# untitled.net
KiCad netlist of a schematic drawn in EAGLE
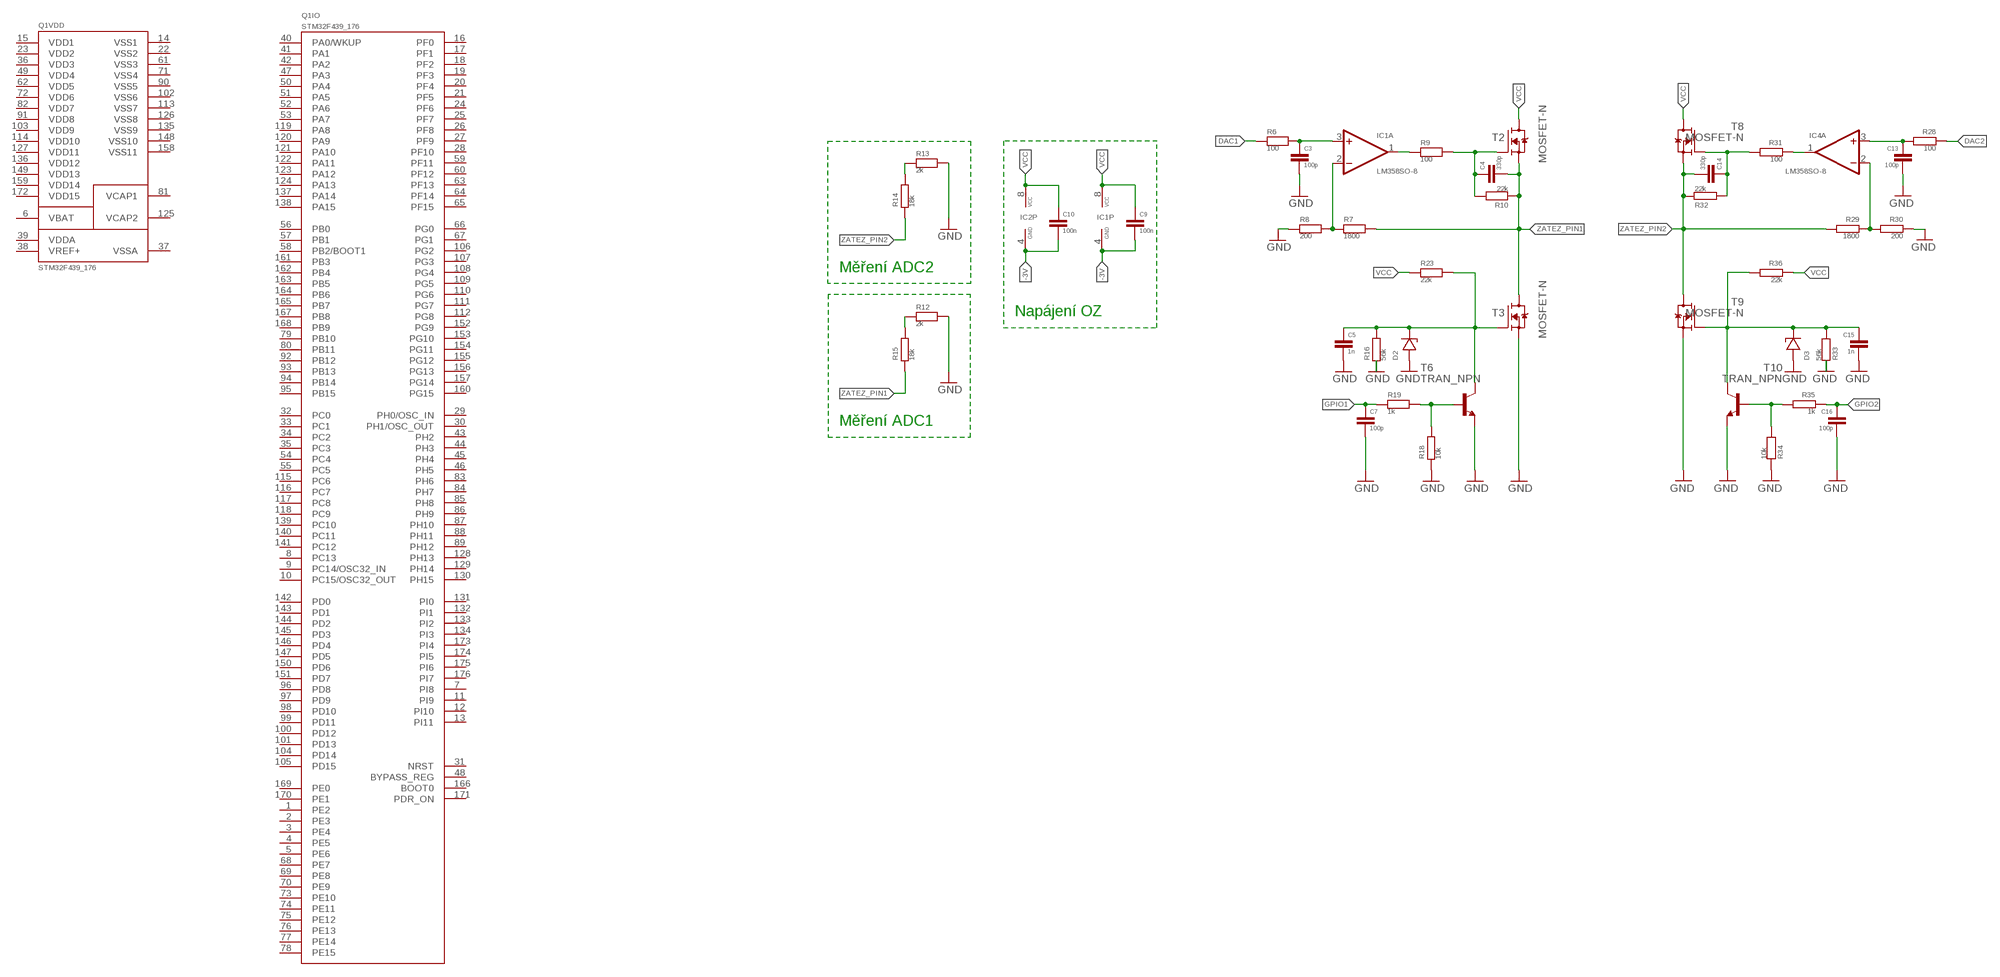
[diagram p0: schematic, sheet 1]

(export (version "E")
  (design (tool "Eeschema 10.0.6"))
  (components
    (comp (ref "C3")
      (value "100p")
      (footprint "eagle-import:0603")
      (libsource (lib "eagle-import") (part "C0603"))
    )
    (comp (ref "C4")
      (value "330p")
      (footprint "eagle-import:0603")
      (libsource (lib "eagle-import") (part "C0603"))
    )
    (comp (ref "C5")
      (value "1n")
      (footprint "eagle-import:0603")
      (libsource (lib "eagle-import") (part "C0603"))
    )
    (comp (ref "C7")
      (value "100p")
      (footprint "eagle-import:0603")
      (libsource (lib "eagle-import") (part "C0603"))
    )
    (comp (ref "C9")
      (value "100n")
      (footprint "eagle-import:0603")
      (libsource (lib "eagle-import") (part "C0603"))
    )
    (comp (ref "C10")
      (value "100n")
      (footprint "eagle-import:0603")
      (libsource (lib "eagle-import") (part "C0603"))
    )
    (comp (ref "C13")
      (value "100p")
      (footprint "eagle-import:0603")
      (libsource (lib "eagle-import") (part "C0603"))
    )
    (comp (ref "C14")
      (value "330p")
      (footprint "eagle-import:0603")
      (libsource (lib "eagle-import") (part "C0603"))
    )
    (comp (ref "C15")
      (value "1n")
      (footprint "eagle-import:0603")
      (libsource (lib "eagle-import") (part "C0603"))
    )
    (comp (ref "C16")
      (value "100p")
      (footprint "eagle-import:0603")
      (libsource (lib "eagle-import") (part "C0603"))
    )
    (comp (ref "D2")
      (value "D_ZENERSMA")
      (footprint "eagle-import:SMA")
      (libsource (lib "eagle-import") (part "D_ZENERSMA"))
    )
    (comp (ref "D3")
      (value "D_ZENERSMA")
      (footprint "eagle-import:SMA")
      (libsource (lib "eagle-import") (part "D_ZENERSMA"))
    )
    (comp (ref "IC1")
      (value "LM358SO-8")
      (footprint "eagle-import:SO-8")
      (libsource (lib "eagle-import") (part "LM358SO-8"))
    )
    (comp (ref "IC2")
      (value "LM358SO-8")
      (footprint "eagle-import:SO-8")
      (libsource (lib "eagle-import") (part "LM358SO-8"))
    )
    (comp (ref "IC4")
      (value "LM358SO-8")
      (footprint "eagle-import:SO-8")
      (libsource (lib "eagle-import") (part "LM358SO-8"))
    )
    (comp (ref "Q1")
      (value "STM32F439_176")
      (footprint "eagle-import:TQFP176")
      (libsource (lib "eagle-import") (part "STM32F439_176"))
    )
    (comp (ref "R6")
      (value "100")
      (footprint "eagle-import:0603")
      (libsource (lib "eagle-import") (part "R0603"))
    )
    (comp (ref "R7")
      (value "1800")
      (footprint "eagle-import:0603")
      (libsource (lib "eagle-import") (part "R0603"))
    )
    (comp (ref "R8")
      (value "200")
      (footprint "eagle-import:0603")
      (libsource (lib "eagle-import") (part "R0603"))
    )
    (comp (ref "R9")
      (value "100")
      (footprint "eagle-import:0603")
      (libsource (lib "eagle-import") (part "R0603"))
    )
    (comp (ref "R10")
      (value "22k")
      (footprint "eagle-import:0603")
      (libsource (lib "eagle-import") (part "R0603"))
    )
    (comp (ref "R12")
      (value "2k")
      (footprint "eagle-import:0603")
      (libsource (lib "eagle-import") (part "R0603"))
    )
    (comp (ref "R13")
      (value "2k")
      (footprint "eagle-import:0603")
      (libsource (lib "eagle-import") (part "R0603"))
    )
    (comp (ref "R14")
      (value "18k")
      (footprint "eagle-import:0603")
      (libsource (lib "eagle-import") (part "R0603"))
    )
    (comp (ref "R15")
      (value "18k")
      (footprint "eagle-import:0603")
      (libsource (lib "eagle-import") (part "R0603"))
    )
    (comp (ref "R16")
      (value "56k")
      (footprint "eagle-import:0603")
      (libsource (lib "eagle-import") (part "R0603"))
    )
    (comp (ref "R18")
      (value "10k")
      (footprint "eagle-import:0603")
      (libsource (lib "eagle-import") (part "R0603"))
    )
    (comp (ref "R19")
      (value "1k")
      (footprint "eagle-import:0603")
      (libsource (lib "eagle-import") (part "R0603"))
    )
    (comp (ref "R23")
      (value "22k")
      (footprint "eagle-import:0603")
      (libsource (lib "eagle-import") (part "R0603"))
    )
    (comp (ref "R28")
      (value "100")
      (footprint "eagle-import:0603")
      (libsource (lib "eagle-import") (part "R0603"))
    )
    (comp (ref "R29")
      (value "1800")
      (footprint "eagle-import:0603")
      (libsource (lib "eagle-import") (part "R0603"))
    )
    (comp (ref "R30")
      (value "200")
      (footprint "eagle-import:0603")
      (libsource (lib "eagle-import") (part "R0603"))
    )
    (comp (ref "R31")
      (value "100")
      (footprint "eagle-import:0603")
      (libsource (lib "eagle-import") (part "R0603"))
    )
    (comp (ref "R32")
      (value "22k")
      (footprint "eagle-import:0603")
      (libsource (lib "eagle-import") (part "R0603"))
    )
    (comp (ref "R33")
      (value "56k")
      (footprint "eagle-import:0603")
      (libsource (lib "eagle-import") (part "R0603"))
    )
    (comp (ref "R34")
      (value "10k")
      (footprint "eagle-import:0603")
      (libsource (lib "eagle-import") (part "R0603"))
    )
    (comp (ref "R35")
      (value "1k")
      (footprint "eagle-import:0603")
      (libsource (lib "eagle-import") (part "R0603"))
    )
    (comp (ref "R36")
      (value "22k")
      (footprint "eagle-import:0603")
      (libsource (lib "eagle-import") (part "R0603"))
    )
    (comp (ref "T2")
      (value "MOSFET-N")
      (footprint "eagle-import:TO220DL")
      (libsource (lib "eagle-import") (part "MOSFET-NTO220DL"))
    )
    (comp (ref "T3")
      (value "MOSFET-N")
      (footprint "eagle-import:TO220DL")
      (libsource (lib "eagle-import") (part "MOSFET-NTO220DL"))
    )
    (comp (ref "T6")
      (value "TRAN_NPN")
      (footprint "eagle-import:SOT23-3")
      (libsource (lib "eagle-import") (part "TRAN_NPN"))
    )
    (comp (ref "T8")
      (value "MOSFET-N")
      (footprint "eagle-import:TO220DL")
      (libsource (lib "eagle-import") (part "MOSFET-NTO220DL"))
    )
    (comp (ref "T9")
      (value "MOSFET-N")
      (footprint "eagle-import:TO220DL")
      (libsource (lib "eagle-import") (part "MOSFET-NTO220DL"))
    )
    (comp (ref "T10")
      (value "TRAN_NPN")
      (footprint "eagle-import:SOT23-3")
      (libsource (lib "eagle-import") (part "TRAN_NPN"))
    )
  )
  (nets
    (net (code "1") (name "-3V") (class "Default")
      (node (ref "C10") (pin "2") (pinfunction "2_2") (pintype "passive"))
      (node (ref "C9") (pin "2") (pinfunction "2_2") (pintype "passive"))
      (node (ref "IC1") (pin "4") (pinfunction "GND_4") (pintype "power_in"))
      (node (ref "IC2") (pin "4") (pinfunction "GND_4") (pintype "power_in"))
    )
    (net (code "2") (name "/VBAT") (class "Default")
      (node (ref "Q1") (pin "6") (pinfunction "VBAT_6") (pintype "power_in"))
    )
    (net (code "3") (name "/VDD1") (class "Default")
      (node (ref "Q1") (pin "15") (pinfunction "VDD1_15") (pintype "power_in"))
    )
    (net (code "4") (name "/VDD2") (class "Default")
      (node (ref "Q1") (pin "23") (pinfunction "VDD2_23") (pintype "power_in"))
    )
    (net (code "5") (name "/VDD3") (class "Default")
      (node (ref "Q1") (pin "36") (pinfunction "VDD3_36") (pintype "power_in"))
    )
    (net (code "6") (name "/VDD4") (class "Default")
      (node (ref "Q1") (pin "49") (pinfunction "VDD4_49") (pintype "power_in"))
    )
    (net (code "7") (name "/VDD5") (class "Default")
      (node (ref "Q1") (pin "62") (pinfunction "VDD5_62") (pintype "power_in"))
    )
    (net (code "8") (name "/VDD6") (class "Default")
      (node (ref "Q1") (pin "72") (pinfunction "VDD6_72") (pintype "power_in"))
    )
    (net (code "9") (name "/VDD7") (class "Default")
      (node (ref "Q1") (pin "82") (pinfunction "VDD7_82") (pintype "power_in"))
    )
    (net (code "10") (name "/VDD8") (class "Default")
      (node (ref "Q1") (pin "91") (pinfunction "VDD8_91") (pintype "power_in"))
    )
    (net (code "11") (name "/VDD9") (class "Default")
      (node (ref "Q1") (pin "103") (pinfunction "VDD9_103") (pintype "power_in"))
    )
    (net (code "12") (name "/VDD10") (class "Default")
      (node (ref "Q1") (pin "114") (pinfunction "VDD10_114") (pintype "power_in"))
    )
    (net (code "13") (name "/VDD11") (class "Default")
      (node (ref "Q1") (pin "127") (pinfunction "VDD11_127") (pintype "power_in"))
    )
    (net (code "14") (name "/VDD12") (class "Default")
      (node (ref "Q1") (pin "136") (pinfunction "VDD12_136") (pintype "power_in"))
    )
    (net (code "15") (name "/VDD13") (class "Default")
      (node (ref "Q1") (pin "149") (pinfunction "VDD13_149") (pintype "power_in"))
    )
    (net (code "16") (name "/VDD14") (class "Default")
      (node (ref "Q1") (pin "159") (pinfunction "VDD14_159") (pintype "power_in"))
    )
    (net (code "17") (name "/VDD15") (class "Default")
      (node (ref "Q1") (pin "172") (pinfunction "VDD15_172") (pintype "power_in"))
    )
    (net (code "18") (name "/VDDA") (class "Default")
      (node (ref "Q1") (pin "39") (pinfunction "VDDA_39") (pintype "power_in"))
    )
    (net (code "19") (name "/VSS1") (class "Default")
      (node (ref "Q1") (pin "14") (pinfunction "VSS1_14") (pintype "power_in"))
    )
    (net (code "20") (name "/VSS2") (class "Default")
      (node (ref "Q1") (pin "22") (pinfunction "VSS2_22") (pintype "power_in"))
    )
    (net (code "21") (name "/VSS3") (class "Default")
      (node (ref "Q1") (pin "61") (pinfunction "VSS3_61") (pintype "power_in"))
    )
    (net (code "22") (name "/VSS4") (class "Default")
      (node (ref "Q1") (pin "71") (pinfunction "VSS4_71") (pintype "power_in"))
    )
    (net (code "23") (name "/VSS5") (class "Default")
      (node (ref "Q1") (pin "90") (pinfunction "VSS5_90") (pintype "power_in"))
    )
    (net (code "24") (name "/VSS6") (class "Default")
      (node (ref "Q1") (pin "102") (pinfunction "VSS6_102") (pintype "power_in"))
    )
    (net (code "25") (name "/VSS7") (class "Default")
      (node (ref "Q1") (pin "113") (pinfunction "VSS7_113") (pintype "power_in"))
    )
    (net (code "26") (name "/VSS8") (class "Default")
      (node (ref "Q1") (pin "126") (pinfunction "VSS8_126") (pintype "power_in"))
    )
    (net (code "27") (name "/VSS9") (class "Default")
      (node (ref "Q1") (pin "135") (pinfunction "VSS9_135") (pintype "power_in"))
    )
    (net (code "28") (name "/VSS10") (class "Default")
      (node (ref "Q1") (pin "148") (pinfunction "VSS10_148") (pintype "power_in"))
    )
    (net (code "29") (name "/VSS11") (class "Default")
      (node (ref "Q1") (pin "158") (pinfunction "VSS11_158") (pintype "power_in"))
    )
    (net (code "30") (name "/VSSA") (class "Default")
      (node (ref "Q1") (pin "37") (pinfunction "VSSA_37") (pintype "power_in"))
    )
    (net (code "31") (name "DAC1") (class "Default")
      (node (ref "R6") (pin "1") (pinfunction "1_1") (pintype "passive"))
    )
    (net (code "32") (name "DAC2") (class "Default")
      (node (ref "R28") (pin "1") (pinfunction "1_1") (pintype "passive"))
    )
    (net (code "33") (name "GND") (class "Default")
      (node (ref "C13") (pin "2") (pinfunction "2_2") (pintype "passive"))
      (node (ref "C15") (pin "2") (pinfunction "2_2") (pintype "passive"))
      (node (ref "C16") (pin "2") (pinfunction "2_2") (pintype "passive"))
      (node (ref "C3") (pin "2") (pinfunction "2_2") (pintype "passive"))
      (node (ref "C5") (pin "2") (pinfunction "2_2") (pintype "passive"))
      (node (ref "C7") (pin "2") (pinfunction "2_2") (pintype "passive"))
      (node (ref "D2") (pin "A") (pinfunction "A_A") (pintype "bidirectional"))
      (node (ref "D3") (pin "A") (pinfunction "A_A") (pintype "bidirectional"))
      (node (ref "R12") (pin "2") (pinfunction "2_2") (pintype "passive"))
      (node (ref "R13") (pin "2") (pinfunction "2_2") (pintype "passive"))
      (node (ref "R16") (pin "1") (pinfunction "1_1") (pintype "passive"))
      (node (ref "R18") (pin "1") (pinfunction "1_1") (pintype "passive"))
      (node (ref "R30") (pin "1") (pinfunction "1_1") (pintype "passive"))
      (node (ref "R33") (pin "1") (pinfunction "1_1") (pintype "passive"))
      (node (ref "R34") (pin "1") (pinfunction "1_1") (pintype "passive"))
      (node (ref "R8") (pin "1") (pinfunction "1_1") (pintype "passive"))
      (node (ref "T10") (pin "2") (pinfunction "E_2") (pintype "passive"))
      (node (ref "T3") (pin "3") (pinfunction "S_3") (pintype "passive"))
      (node (ref "T6") (pin "2") (pinfunction "E_2") (pintype "passive"))
      (node (ref "T9") (pin "3") (pinfunction "S_3") (pintype "passive"))
    )
    (net (code "34") (name "GPIO1") (class "Default")
      (node (ref "C7") (pin "1") (pinfunction "1_1") (pintype "passive"))
      (node (ref "R19") (pin "1") (pinfunction "1_1") (pintype "passive"))
    )
    (net (code "35") (name "GPIO2") (class "Default")
      (node (ref "C16") (pin "1") (pinfunction "1_1") (pintype "passive"))
      (node (ref "R35") (pin "1") (pinfunction "1_1") (pintype "passive"))
    )
    (net (code "36") (name "Net-(D2-K)") (class "Default")
      (node (ref "C5") (pin "1") (pinfunction "1_1") (pintype "passive"))
      (node (ref "D2") (pin "C") (pinfunction "K_C") (pintype "bidirectional"))
      (node (ref "R16") (pin "2") (pinfunction "2_2") (pintype "passive"))
      (node (ref "R23") (pin "2") (pinfunction "2_2") (pintype "passive"))
      (node (ref "T3") (pin "1") (pinfunction "G_1") (pintype "passive"))
      (node (ref "T6") (pin "3") (pinfunction "C_3") (pintype "passive"))
    )
    (net (code "37") (name "Net-(D3-K)") (class "Default")
      (node (ref "C15") (pin "1") (pinfunction "1_1") (pintype "passive"))
      (node (ref "D3") (pin "C") (pinfunction "K_C") (pintype "bidirectional"))
      (node (ref "R33") (pin "2") (pinfunction "2_2") (pintype "passive"))
      (node (ref "R36") (pin "2") (pinfunction "2_2") (pintype "passive"))
      (node (ref "T10") (pin "3") (pinfunction "C_3") (pintype "passive"))
      (node (ref "T9") (pin "1") (pinfunction "G_1") (pintype "passive"))
    )
    (net (code "38") (name "Net-(IC1A-+IN)") (class "Default")
      (node (ref "C3") (pin "1") (pinfunction "1_1") (pintype "passive"))
      (node (ref "IC1") (pin "3") (pinfunction "+IN_3") (pintype "input"))
      (node (ref "R6") (pin "2") (pinfunction "2_2") (pintype "passive"))
    )
    (net (code "39") (name "Net-(IC1A--IN)") (class "Default")
      (node (ref "IC1") (pin "2") (pinfunction "-IN_2") (pintype "input"))
      (node (ref "R7") (pin "1") (pinfunction "1_1") (pintype "passive"))
      (node (ref "R8") (pin "2") (pinfunction "2_2") (pintype "passive"))
    )
    (net (code "40") (name "Net-(IC1A-OUT)") (class "Default")
      (node (ref "IC1") (pin "1") (pinfunction "OUT_1") (pintype "output"))
      (node (ref "R9") (pin "1") (pinfunction "1_1") (pintype "passive"))
    )
    (net (code "41") (name "Net-(IC4A-+IN)") (class "Default")
      (node (ref "C13") (pin "1") (pinfunction "1_1") (pintype "passive"))
      (node (ref "IC4") (pin "3") (pinfunction "+IN_3") (pintype "input"))
      (node (ref "R28") (pin "2") (pinfunction "2_2") (pintype "passive"))
    )
    (net (code "42") (name "Net-(IC4A--IN)") (class "Default")
      (node (ref "IC4") (pin "2") (pinfunction "-IN_2") (pintype "input"))
      (node (ref "R29") (pin "1") (pinfunction "1_1") (pintype "passive"))
      (node (ref "R30") (pin "2") (pinfunction "2_2") (pintype "passive"))
    )
    (net (code "43") (name "Net-(IC4A-OUT)") (class "Default")
      (node (ref "IC4") (pin "1") (pinfunction "OUT_1") (pintype "output"))
      (node (ref "R31") (pin "1") (pinfunction "1_1") (pintype "passive"))
    )
    (net (code "44") (name "Net-(R12-Pad1)") (class "Default")
      (node (ref "R12") (pin "1") (pinfunction "1_1") (pintype "passive"))
      (node (ref "R15") (pin "2") (pinfunction "2_2") (pintype "passive"))
    )
    (net (code "45") (name "Net-(R13-Pad1)") (class "Default")
      (node (ref "R13") (pin "1") (pinfunction "1_1") (pintype "passive"))
      (node (ref "R14") (pin "2") (pinfunction "2_2") (pintype "passive"))
    )
    (net (code "46") (name "Net-(T2-G)") (class "Default")
      (node (ref "C4") (pin "1") (pinfunction "1_1") (pintype "passive"))
      (node (ref "R10") (pin "2") (pinfunction "2_2") (pintype "passive"))
      (node (ref "R9") (pin "2") (pinfunction "2_2") (pintype "passive"))
      (node (ref "T2") (pin "1") (pinfunction "G_1") (pintype "passive"))
    )
    (net (code "47") (name "Net-(T6-B)") (class "Default")
      (node (ref "R18") (pin "2") (pinfunction "2_2") (pintype "passive"))
      (node (ref "R19") (pin "2") (pinfunction "2_2") (pintype "passive"))
      (node (ref "T6") (pin "1") (pinfunction "B_1") (pintype "passive"))
    )
    (net (code "48") (name "Net-(T8-G)") (class "Default")
      (node (ref "C14") (pin "1") (pinfunction "1_1") (pintype "passive"))
      (node (ref "R31") (pin "2") (pinfunction "2_2") (pintype "passive"))
      (node (ref "R32") (pin "2") (pinfunction "2_2") (pintype "passive"))
      (node (ref "T8") (pin "1") (pinfunction "G_1") (pintype "passive"))
    )
    (net (code "49") (name "Net-(T10-B)") (class "Default")
      (node (ref "R34") (pin "2") (pinfunction "2_2") (pintype "passive"))
      (node (ref "R35") (pin "2") (pinfunction "2_2") (pintype "passive"))
      (node (ref "T10") (pin "1") (pinfunction "B_1") (pintype "passive"))
    )
    (net (code "50") (name "VCC") (class "Default")
      (node (ref "C10") (pin "1") (pinfunction "1_1") (pintype "passive"))
      (node (ref "C9") (pin "1") (pinfunction "1_1") (pintype "passive"))
      (node (ref "IC1") (pin "8") (pinfunction "VCC_8") (pintype "power_in"))
      (node (ref "IC2") (pin "8") (pinfunction "VCC_8") (pintype "power_in"))
      (node (ref "R23") (pin "1") (pinfunction "1_1") (pintype "passive"))
      (node (ref "R36") (pin "1") (pinfunction "1_1") (pintype "passive"))
      (node (ref "T2") (pin "2") (pinfunction "D_2") (pintype "passive"))
      (node (ref "T8") (pin "2") (pinfunction "D_2") (pintype "passive"))
    )
    (net (code "51") (name "ZATEZ_PIN1") (class "Default")
      (node (ref "C4") (pin "2") (pinfunction "2_2") (pintype "passive"))
      (node (ref "R10") (pin "1") (pinfunction "1_1") (pintype "passive"))
      (node (ref "R15") (pin "1") (pinfunction "1_1") (pintype "passive"))
      (node (ref "R7") (pin "2") (pinfunction "2_2") (pintype "passive"))
      (node (ref "T2") (pin "3") (pinfunction "S_3") (pintype "passive"))
      (node (ref "T3") (pin "2") (pinfunction "D_2") (pintype "passive"))
    )
    (net (code "52") (name "ZATEZ_PIN2") (class "Default")
      (node (ref "C14") (pin "2") (pinfunction "2_2") (pintype "passive"))
      (node (ref "R14") (pin "1") (pinfunction "1_1") (pintype "passive"))
      (node (ref "R29") (pin "2") (pinfunction "2_2") (pintype "passive"))
      (node (ref "R32") (pin "1") (pinfunction "1_1") (pintype "passive"))
      (node (ref "T8") (pin "3") (pinfunction "S_3") (pintype "passive"))
      (node (ref "T9") (pin "2") (pinfunction "D_2") (pintype "passive"))
    )
    (net (code "53") (name "unconnected-(Q1A-BOOT0-Pad166)") (class "Default")
      (node (ref "Q1") (pin "166") (pinfunction "BOOT0_166") (pintype "bidirectional"))
    )
    (net (code "54") (name "unconnected-(Q1A-BYPASS_REG-Pad48)") (class "Default")
      (node (ref "Q1") (pin "48") (pinfunction "BYPASS_REG_48") (pintype "bidirectional"))
    )
    (net (code "55") (name "unconnected-(Q1A-NRST-Pad31)") (class "Default")
      (node (ref "Q1") (pin "31") (pinfunction "NRST_31") (pintype "bidirectional"))
    )
    (net (code "56") (name "unconnected-(Q1A-PA0{slash}WKUP-Pad40)") (class "Default")
      (node (ref "Q1") (pin "40") (pinfunction "PA0/WKUP_40") (pintype "bidirectional"))
    )
    (net (code "57") (name "unconnected-(Q1A-PA1-Pad41)") (class "Default")
      (node (ref "Q1") (pin "41") (pinfunction "PA1_41") (pintype "bidirectional"))
    )
    (net (code "58") (name "unconnected-(Q1A-PA2-Pad42)") (class "Default")
      (node (ref "Q1") (pin "42") (pinfunction "PA2_42") (pintype "bidirectional"))
    )
    (net (code "59") (name "unconnected-(Q1A-PA3-Pad47)") (class "Default")
      (node (ref "Q1") (pin "47") (pinfunction "PA3_47") (pintype "bidirectional"))
    )
    (net (code "60") (name "unconnected-(Q1A-PA4-Pad50)") (class "Default")
      (node (ref "Q1") (pin "50") (pinfunction "PA4_50") (pintype "bidirectional"))
    )
    (net (code "61") (name "unconnected-(Q1A-PA5-Pad51)") (class "Default")
      (node (ref "Q1") (pin "51") (pinfunction "PA5_51") (pintype "bidirectional"))
    )
    (net (code "62") (name "unconnected-(Q1A-PA6-Pad52)") (class "Default")
      (node (ref "Q1") (pin "52") (pinfunction "PA6_52") (pintype "bidirectional"))
    )
    (net (code "63") (name "unconnected-(Q1A-PA7-Pad53)") (class "Default")
      (node (ref "Q1") (pin "53") (pinfunction "PA7_53") (pintype "bidirectional"))
    )
    (net (code "64") (name "unconnected-(Q1A-PA8-Pad119)") (class "Default")
      (node (ref "Q1") (pin "119") (pinfunction "PA8_119") (pintype "bidirectional"))
    )
    (net (code "65") (name "unconnected-(Q1A-PA9-Pad120)") (class "Default")
      (node (ref "Q1") (pin "120") (pinfunction "PA9_120") (pintype "bidirectional"))
    )
    (net (code "66") (name "unconnected-(Q1A-PA10-Pad121)") (class "Default")
      (node (ref "Q1") (pin "121") (pinfunction "PA10_121") (pintype "bidirectional"))
    )
    (net (code "67") (name "unconnected-(Q1A-PA11-Pad122)") (class "Default")
      (node (ref "Q1") (pin "122") (pinfunction "PA11_122") (pintype "bidirectional"))
    )
    (net (code "68") (name "unconnected-(Q1A-PA12-Pad123)") (class "Default")
      (node (ref "Q1") (pin "123") (pinfunction "PA12_123") (pintype "bidirectional"))
    )
    (net (code "69") (name "unconnected-(Q1A-PA13-Pad124)") (class "Default")
      (node (ref "Q1") (pin "124") (pinfunction "PA13_124") (pintype "bidirectional"))
    )
    (net (code "70") (name "unconnected-(Q1A-PA14-Pad137)") (class "Default")
      (node (ref "Q1") (pin "137") (pinfunction "PA14_137") (pintype "bidirectional"))
    )
    (net (code "71") (name "unconnected-(Q1A-PA15-Pad138)") (class "Default")
      (node (ref "Q1") (pin "138") (pinfunction "PA15_138") (pintype "bidirectional"))
    )
    (net (code "72") (name "unconnected-(Q1A-PB0-Pad56)") (class "Default")
      (node (ref "Q1") (pin "56") (pinfunction "PB0_56") (pintype "bidirectional"))
    )
    (net (code "73") (name "unconnected-(Q1A-PB1-Pad57)") (class "Default")
      (node (ref "Q1") (pin "57") (pinfunction "PB1_57") (pintype "bidirectional"))
    )
    (net (code "74") (name "unconnected-(Q1A-PB2{slash}BOOT1-Pad58)") (class "Default")
      (node (ref "Q1") (pin "58") (pinfunction "PB2/BOOT1_58") (pintype "bidirectional"))
    )
    (net (code "75") (name "unconnected-(Q1A-PB3-Pad161)") (class "Default")
      (node (ref "Q1") (pin "161") (pinfunction "PB3_161") (pintype "bidirectional"))
    )
    (net (code "76") (name "unconnected-(Q1A-PB4-Pad162)") (class "Default")
      (node (ref "Q1") (pin "162") (pinfunction "PB4_162") (pintype "bidirectional"))
    )
    (net (code "77") (name "unconnected-(Q1A-PB5-Pad163)") (class "Default")
      (node (ref "Q1") (pin "163") (pinfunction "PB5_163") (pintype "bidirectional"))
    )
    (net (code "78") (name "unconnected-(Q1A-PB6-Pad164)") (class "Default")
      (node (ref "Q1") (pin "164") (pinfunction "PB6_164") (pintype "bidirectional"))
    )
    (net (code "79") (name "unconnected-(Q1A-PB7-Pad165)") (class "Default")
      (node (ref "Q1") (pin "165") (pinfunction "PB7_165") (pintype "bidirectional"))
    )
    (net (code "80") (name "unconnected-(Q1A-PB8-Pad167)") (class "Default")
      (node (ref "Q1") (pin "167") (pinfunction "PB8_167") (pintype "bidirectional"))
    )
    (net (code "81") (name "unconnected-(Q1A-PB9-Pad168)") (class "Default")
      (node (ref "Q1") (pin "168") (pinfunction "PB9_168") (pintype "bidirectional"))
    )
    (net (code "82") (name "unconnected-(Q1A-PB10-Pad79)") (class "Default")
      (node (ref "Q1") (pin "79") (pinfunction "PB10_79") (pintype "bidirectional"))
    )
    (net (code "83") (name "unconnected-(Q1A-PB11-Pad80)") (class "Default")
      (node (ref "Q1") (pin "80") (pinfunction "PB11_80") (pintype "bidirectional"))
    )
    (net (code "84") (name "unconnected-(Q1A-PB12-Pad92)") (class "Default")
      (node (ref "Q1") (pin "92") (pinfunction "PB12_92") (pintype "bidirectional"))
    )
    (net (code "85") (name "unconnected-(Q1A-PB13-Pad93)") (class "Default")
      (node (ref "Q1") (pin "93") (pinfunction "PB13_93") (pintype "bidirectional"))
    )
    (net (code "86") (name "unconnected-(Q1A-PB14-Pad94)") (class "Default")
      (node (ref "Q1") (pin "94") (pinfunction "PB14_94") (pintype "bidirectional"))
    )
    (net (code "87") (name "unconnected-(Q1A-PB15-Pad95)") (class "Default")
      (node (ref "Q1") (pin "95") (pinfunction "PB15_95") (pintype "bidirectional"))
    )
    (net (code "88") (name "unconnected-(Q1A-PC0-Pad32)") (class "Default")
      (node (ref "Q1") (pin "32") (pinfunction "PC0_32") (pintype "bidirectional"))
    )
    (net (code "89") (name "unconnected-(Q1A-PC1-Pad33)") (class "Default")
      (node (ref "Q1") (pin "33") (pinfunction "PC1_33") (pintype "bidirectional"))
    )
    (net (code "90") (name "unconnected-(Q1A-PC2-Pad34)") (class "Default")
      (node (ref "Q1") (pin "34") (pinfunction "PC2_34") (pintype "bidirectional"))
    )
    (net (code "91") (name "unconnected-(Q1A-PC3-Pad35)") (class "Default")
      (node (ref "Q1") (pin "35") (pinfunction "PC3_35") (pintype "bidirectional"))
    )
    (net (code "92") (name "unconnected-(Q1A-PC4-Pad54)") (class "Default")
      (node (ref "Q1") (pin "54") (pinfunction "PC4_54") (pintype "bidirectional"))
    )
    (net (code "93") (name "unconnected-(Q1A-PC5-Pad55)") (class "Default")
      (node (ref "Q1") (pin "55") (pinfunction "PC5_55") (pintype "bidirectional"))
    )
    (net (code "94") (name "unconnected-(Q1A-PC6-Pad115)") (class "Default")
      (node (ref "Q1") (pin "115") (pinfunction "PC6_115") (pintype "bidirectional"))
    )
    (net (code "95") (name "unconnected-(Q1A-PC7-Pad116)") (class "Default")
      (node (ref "Q1") (pin "116") (pinfunction "PC7_116") (pintype "bidirectional"))
    )
    (net (code "96") (name "unconnected-(Q1A-PC8-Pad117)") (class "Default")
      (node (ref "Q1") (pin "117") (pinfunction "PC8_117") (pintype "bidirectional"))
    )
    (net (code "97") (name "unconnected-(Q1A-PC9-Pad118)") (class "Default")
      (node (ref "Q1") (pin "118") (pinfunction "PC9_118") (pintype "bidirectional"))
    )
    (net (code "98") (name "unconnected-(Q1A-PC10-Pad139)") (class "Default")
      (node (ref "Q1") (pin "139") (pinfunction "PC10_139") (pintype "bidirectional"))
    )
    (net (code "99") (name "unconnected-(Q1A-PC11-Pad140)") (class "Default")
      (node (ref "Q1") (pin "140") (pinfunction "PC11_140") (pintype "bidirectional"))
    )
    (net (code "100") (name "unconnected-(Q1A-PC12-Pad141)") (class "Default")
      (node (ref "Q1") (pin "141") (pinfunction "PC12_141") (pintype "bidirectional"))
    )
    (net (code "101") (name "unconnected-(Q1A-PC13-Pad8)") (class "Default")
      (node (ref "Q1") (pin "8") (pinfunction "PC13_8") (pintype "bidirectional"))
    )
    (net (code "102") (name "unconnected-(Q1A-PC14{slash}OSC32_IN-Pad9)") (class "Default")
      (node (ref "Q1") (pin "9") (pinfunction "PC14/OSC32_IN_9") (pintype "bidirectional"))
    )
    (net (code "103") (name "unconnected-(Q1A-PC15{slash}OSC32_OUT-Pad10)") (class "Default")
      (node (ref "Q1") (pin "10") (pinfunction "PC15/OSC32_OUT_10") (pintype "bidirectional"))
    )
    (net (code "104") (name "unconnected-(Q1A-PD0-Pad142)") (class "Default")
      (node (ref "Q1") (pin "142") (pinfunction "PD0_142") (pintype "bidirectional"))
    )
    (net (code "105") (name "unconnected-(Q1A-PD1-Pad143)") (class "Default")
      (node (ref "Q1") (pin "143") (pinfunction "PD1_143") (pintype "bidirectional"))
    )
    (net (code "106") (name "unconnected-(Q1A-PD2-Pad144)") (class "Default")
      (node (ref "Q1") (pin "144") (pinfunction "PD2_144") (pintype "bidirectional"))
    )
    (net (code "107") (name "unconnected-(Q1A-PD3-Pad145)") (class "Default")
      (node (ref "Q1") (pin "145") (pinfunction "PD3_145") (pintype "bidirectional"))
    )
    (net (code "108") (name "unconnected-(Q1A-PD4-Pad146)") (class "Default")
      (node (ref "Q1") (pin "146") (pinfunction "PD4_146") (pintype "bidirectional"))
    )
    (net (code "109") (name "unconnected-(Q1A-PD5-Pad147)") (class "Default")
      (node (ref "Q1") (pin "147") (pinfunction "PD5_147") (pintype "bidirectional"))
    )
    (net (code "110") (name "unconnected-(Q1A-PD6-Pad150)") (class "Default")
      (node (ref "Q1") (pin "150") (pinfunction "PD6_150") (pintype "bidirectional"))
    )
    (net (code "111") (name "unconnected-(Q1A-PD7-Pad151)") (class "Default")
      (node (ref "Q1") (pin "151") (pinfunction "PD7_151") (pintype "bidirectional"))
    )
    (net (code "112") (name "unconnected-(Q1A-PD8-Pad96)") (class "Default")
      (node (ref "Q1") (pin "96") (pinfunction "PD8_96") (pintype "bidirectional"))
    )
    (net (code "113") (name "unconnected-(Q1A-PD9-Pad97)") (class "Default")
      (node (ref "Q1") (pin "97") (pinfunction "PD9_97") (pintype "bidirectional"))
    )
    (net (code "114") (name "unconnected-(Q1A-PD10-Pad98)") (class "Default")
      (node (ref "Q1") (pin "98") (pinfunction "PD10_98") (pintype "bidirectional"))
    )
    (net (code "115") (name "unconnected-(Q1A-PD11-Pad99)") (class "Default")
      (node (ref "Q1") (pin "99") (pinfunction "PD11_99") (pintype "bidirectional"))
    )
    (net (code "116") (name "unconnected-(Q1A-PD12-Pad100)") (class "Default")
      (node (ref "Q1") (pin "100") (pinfunction "PD12_100") (pintype "bidirectional"))
    )
    (net (code "117") (name "unconnected-(Q1A-PD13-Pad101)") (class "Default")
      (node (ref "Q1") (pin "101") (pinfunction "PD13_101") (pintype "bidirectional"))
    )
    (net (code "118") (name "unconnected-(Q1A-PD14-Pad104)") (class "Default")
      (node (ref "Q1") (pin "104") (pinfunction "PD14_104") (pintype "bidirectional"))
    )
    (net (code "119") (name "unconnected-(Q1A-PD15-Pad105)") (class "Default")
      (node (ref "Q1") (pin "105") (pinfunction "PD15_105") (pintype "bidirectional"))
    )
    (net (code "120") (name "unconnected-(Q1A-PDR_ON-Pad171)") (class "Default")
      (node (ref "Q1") (pin "171") (pinfunction "PDR_ON_171") (pintype "bidirectional"))
    )
    (net (code "121") (name "unconnected-(Q1A-PE0-Pad169)") (class "Default")
      (node (ref "Q1") (pin "169") (pinfunction "PE0_169") (pintype "bidirectional"))
    )
    (net (code "122") (name "unconnected-(Q1A-PE1-Pad170)") (class "Default")
      (node (ref "Q1") (pin "170") (pinfunction "PE1_170") (pintype "bidirectional"))
    )
    (net (code "123") (name "unconnected-(Q1A-PE2-Pad1)") (class "Default")
      (node (ref "Q1") (pin "1") (pinfunction "PE2_1") (pintype "bidirectional"))
    )
    (net (code "124") (name "unconnected-(Q1A-PE3-Pad2)") (class "Default")
      (node (ref "Q1") (pin "2") (pinfunction "PE3_2") (pintype "bidirectional"))
    )
    (net (code "125") (name "unconnected-(Q1A-PE4-Pad3)") (class "Default")
      (node (ref "Q1") (pin "3") (pinfunction "PE4_3") (pintype "bidirectional"))
    )
    (net (code "126") (name "unconnected-(Q1A-PE5-Pad4)") (class "Default")
      (node (ref "Q1") (pin "4") (pinfunction "PE5_4") (pintype "bidirectional"))
    )
    (net (code "127") (name "unconnected-(Q1A-PE6-Pad5)") (class "Default")
      (node (ref "Q1") (pin "5") (pinfunction "PE6_5") (pintype "bidirectional"))
    )
    (net (code "128") (name "unconnected-(Q1A-PE7-Pad68)") (class "Default")
      (node (ref "Q1") (pin "68") (pinfunction "PE7_68") (pintype "bidirectional"))
    )
    (net (code "129") (name "unconnected-(Q1A-PE8-Pad69)") (class "Default")
      (node (ref "Q1") (pin "69") (pinfunction "PE8_69") (pintype "bidirectional"))
    )
    (net (code "130") (name "unconnected-(Q1A-PE9-Pad70)") (class "Default")
      (node (ref "Q1") (pin "70") (pinfunction "PE9_70") (pintype "bidirectional"))
    )
    (net (code "131") (name "unconnected-(Q1A-PE10-Pad73)") (class "Default")
      (node (ref "Q1") (pin "73") (pinfunction "PE10_73") (pintype "bidirectional"))
    )
    (net (code "132") (name "unconnected-(Q1A-PE11-Pad74)") (class "Default")
      (node (ref "Q1") (pin "74") (pinfunction "PE11_74") (pintype "bidirectional"))
    )
    (net (code "133") (name "unconnected-(Q1A-PE12-Pad75)") (class "Default")
      (node (ref "Q1") (pin "75") (pinfunction "PE12_75") (pintype "bidirectional"))
    )
    (net (code "134") (name "unconnected-(Q1A-PE13-Pad76)") (class "Default")
      (node (ref "Q1") (pin "76") (pinfunction "PE13_76") (pintype "bidirectional"))
    )
    (net (code "135") (name "unconnected-(Q1A-PE14-Pad77)") (class "Default")
      (node (ref "Q1") (pin "77") (pinfunction "PE14_77") (pintype "bidirectional"))
    )
    (net (code "136") (name "unconnected-(Q1A-PE15-Pad78)") (class "Default")
      (node (ref "Q1") (pin "78") (pinfunction "PE15_78") (pintype "bidirectional"))
    )
    (net (code "137") (name "unconnected-(Q1A-PF0-Pad16)") (class "Default")
      (node (ref "Q1") (pin "16") (pinfunction "PF0_16") (pintype "bidirectional"))
    )
    (net (code "138") (name "unconnected-(Q1A-PF1-Pad17)") (class "Default")
      (node (ref "Q1") (pin "17") (pinfunction "PF1_17") (pintype "bidirectional"))
    )
    (net (code "139") (name "unconnected-(Q1A-PF2-Pad18)") (class "Default")
      (node (ref "Q1") (pin "18") (pinfunction "PF2_18") (pintype "bidirectional"))
    )
    (net (code "140") (name "unconnected-(Q1A-PF3-Pad19)") (class "Default")
      (node (ref "Q1") (pin "19") (pinfunction "PF3_19") (pintype "bidirectional"))
    )
    (net (code "141") (name "unconnected-(Q1A-PF4-Pad20)") (class "Default")
      (node (ref "Q1") (pin "20") (pinfunction "PF4_20") (pintype "bidirectional"))
    )
    (net (code "142") (name "unconnected-(Q1A-PF5-Pad21)") (class "Default")
      (node (ref "Q1") (pin "21") (pinfunction "PF5_21") (pintype "bidirectional"))
    )
    (net (code "143") (name "unconnected-(Q1A-PF6-Pad24)") (class "Default")
      (node (ref "Q1") (pin "24") (pinfunction "PF6_24") (pintype "bidirectional"))
    )
    (net (code "144") (name "unconnected-(Q1A-PF7-Pad25)") (class "Default")
      (node (ref "Q1") (pin "25") (pinfunction "PF7_25") (pintype "bidirectional"))
    )
    (net (code "145") (name "unconnected-(Q1A-PF8-Pad26)") (class "Default")
      (node (ref "Q1") (pin "26") (pinfunction "PF8_26") (pintype "bidirectional"))
    )
    (net (code "146") (name "unconnected-(Q1A-PF9-Pad27)") (class "Default")
      (node (ref "Q1") (pin "27") (pinfunction "PF9_27") (pintype "bidirectional"))
    )
    (net (code "147") (name "unconnected-(Q1A-PF10-Pad28)") (class "Default")
      (node (ref "Q1") (pin "28") (pinfunction "PF10_28") (pintype "bidirectional"))
    )
    (net (code "148") (name "unconnected-(Q1A-PF11-Pad59)") (class "Default")
      (node (ref "Q1") (pin "59") (pinfunction "PF11_59") (pintype "bidirectional"))
    )
    (net (code "149") (name "unconnected-(Q1A-PF12-Pad60)") (class "Default")
      (node (ref "Q1") (pin "60") (pinfunction "PF12_60") (pintype "bidirectional"))
    )
    (net (code "150") (name "unconnected-(Q1A-PF13-Pad63)") (class "Default")
      (node (ref "Q1") (pin "63") (pinfunction "PF13_63") (pintype "bidirectional"))
    )
    (net (code "151") (name "unconnected-(Q1A-PF14-Pad64)") (class "Default")
      (node (ref "Q1") (pin "64") (pinfunction "PF14_64") (pintype "bidirectional"))
    )
    (net (code "152") (name "unconnected-(Q1A-PF15-Pad65)") (class "Default")
      (node (ref "Q1") (pin "65") (pinfunction "PF15_65") (pintype "bidirectional"))
    )
    (net (code "153") (name "unconnected-(Q1A-PG0-Pad66)") (class "Default")
      (node (ref "Q1") (pin "66") (pinfunction "PG0_66") (pintype "bidirectional"))
    )
    (net (code "154") (name "unconnected-(Q1A-PG1-Pad67)") (class "Default")
      (node (ref "Q1") (pin "67") (pinfunction "PG1_67") (pintype "bidirectional"))
    )
    (net (code "155") (name "unconnected-(Q1A-PG2-Pad106)") (class "Default")
      (node (ref "Q1") (pin "106") (pinfunction "PG2_106") (pintype "bidirectional"))
    )
    (net (code "156") (name "unconnected-(Q1A-PG3-Pad107)") (class "Default")
      (node (ref "Q1") (pin "107") (pinfunction "PG3_107") (pintype "bidirectional"))
    )
    (net (code "157") (name "unconnected-(Q1A-PG4-Pad108)") (class "Default")
      (node (ref "Q1") (pin "108") (pinfunction "PG4_108") (pintype "bidirectional"))
    )
    (net (code "158") (name "unconnected-(Q1A-PG5-Pad109)") (class "Default")
      (node (ref "Q1") (pin "109") (pinfunction "PG5_109") (pintype "bidirectional"))
    )
    (net (code "159") (name "unconnected-(Q1A-PG6-Pad110)") (class "Default")
      (node (ref "Q1") (pin "110") (pinfunction "PG6_110") (pintype "bidirectional"))
    )
    (net (code "160") (name "unconnected-(Q1A-PG7-Pad111)") (class "Default")
      (node (ref "Q1") (pin "111") (pinfunction "PG7_111") (pintype "bidirectional"))
    )
    (net (code "161") (name "unconnected-(Q1A-PG8-Pad112)") (class "Default")
      (node (ref "Q1") (pin "112") (pinfunction "PG8_112") (pintype "bidirectional"))
    )
    (net (code "162") (name "unconnected-(Q1A-PG9-Pad152)") (class "Default")
      (node (ref "Q1") (pin "152") (pinfunction "PG9_152") (pintype "bidirectional"))
    )
    (net (code "163") (name "unconnected-(Q1A-PG10-Pad153)") (class "Default")
      (node (ref "Q1") (pin "153") (pinfunction "PG10_153") (pintype "bidirectional"))
    )
    (net (code "164") (name "unconnected-(Q1A-PG11-Pad154)") (class "Default")
      (node (ref "Q1") (pin "154") (pinfunction "PG11_154") (pintype "bidirectional"))
    )
    (net (code "165") (name "unconnected-(Q1A-PG12-Pad155)") (class "Default")
      (node (ref "Q1") (pin "155") (pinfunction "PG12_155") (pintype "bidirectional"))
    )
    (net (code "166") (name "unconnected-(Q1A-PG13-Pad156)") (class "Default")
      (node (ref "Q1") (pin "156") (pinfunction "PG13_156") (pintype "bidirectional"))
    )
    (net (code "167") (name "unconnected-(Q1A-PG14-Pad157)") (class "Default")
      (node (ref "Q1") (pin "157") (pinfunction "PG14_157") (pintype "bidirectional"))
    )
    (net (code "168") (name "unconnected-(Q1A-PG15-Pad160)") (class "Default")
      (node (ref "Q1") (pin "160") (pinfunction "PG15_160") (pintype "bidirectional"))
    )
    (net (code "169") (name "unconnected-(Q1A-PH0{slash}OSC_IN-Pad29)") (class "Default")
      (node (ref "Q1") (pin "29") (pinfunction "PH0/OSC_IN_29") (pintype "bidirectional"))
    )
    (net (code "170") (name "unconnected-(Q1A-PH1{slash}OSC_OUT-Pad30)") (class "Default")
      (node (ref "Q1") (pin "30") (pinfunction "PH1/OSC_OUT_30") (pintype "bidirectional"))
    )
    (net (code "171") (name "unconnected-(Q1A-PH2-Pad43)") (class "Default")
      (node (ref "Q1") (pin "43") (pinfunction "PH2_43") (pintype "bidirectional"))
    )
    (net (code "172") (name "unconnected-(Q1A-PH3-Pad44)") (class "Default")
      (node (ref "Q1") (pin "44") (pinfunction "PH3_44") (pintype "bidirectional"))
    )
    (net (code "173") (name "unconnected-(Q1A-PH4-Pad45)") (class "Default")
      (node (ref "Q1") (pin "45") (pinfunction "PH4_45") (pintype "bidirectional"))
    )
    (net (code "174") (name "unconnected-(Q1A-PH5-Pad46)") (class "Default")
      (node (ref "Q1") (pin "46") (pinfunction "PH5_46") (pintype "bidirectional"))
    )
    (net (code "175") (name "unconnected-(Q1A-PH6-Pad83)") (class "Default")
      (node (ref "Q1") (pin "83") (pinfunction "PH6_83") (pintype "bidirectional"))
    )
    (net (code "176") (name "unconnected-(Q1A-PH7-Pad84)") (class "Default")
      (node (ref "Q1") (pin "84") (pinfunction "PH7_84") (pintype "bidirectional"))
    )
    (net (code "177") (name "unconnected-(Q1A-PH8-Pad85)") (class "Default")
      (node (ref "Q1") (pin "85") (pinfunction "PH8_85") (pintype "bidirectional"))
    )
    (net (code "178") (name "unconnected-(Q1A-PH9-Pad86)") (class "Default")
      (node (ref "Q1") (pin "86") (pinfunction "PH9_86") (pintype "bidirectional"))
    )
    (net (code "179") (name "unconnected-(Q1A-PH10-Pad87)") (class "Default")
      (node (ref "Q1") (pin "87") (pinfunction "PH10_87") (pintype "bidirectional"))
    )
    (net (code "180") (name "unconnected-(Q1A-PH11-Pad88)") (class "Default")
      (node (ref "Q1") (pin "88") (pinfunction "PH11_88") (pintype "bidirectional"))
    )
    (net (code "181") (name "unconnected-(Q1A-PH12-Pad89)") (class "Default")
      (node (ref "Q1") (pin "89") (pinfunction "PH12_89") (pintype "bidirectional"))
    )
    (net (code "182") (name "unconnected-(Q1A-PH13-Pad128)") (class "Default")
      (node (ref "Q1") (pin "128") (pinfunction "PH13_128") (pintype "bidirectional"))
    )
    (net (code "183") (name "unconnected-(Q1A-PH14-Pad129)") (class "Default")
      (node (ref "Q1") (pin "129") (pinfunction "PH14_129") (pintype "bidirectional"))
    )
    (net (code "184") (name "unconnected-(Q1A-PH15-Pad130)") (class "Default")
      (node (ref "Q1") (pin "130") (pinfunction "PH15_130") (pintype "bidirectional"))
    )
    (net (code "185") (name "unconnected-(Q1A-PI0-Pad131)") (class "Default")
      (node (ref "Q1") (pin "131") (pinfunction "PI0_131") (pintype "bidirectional"))
    )
    (net (code "186") (name "unconnected-(Q1A-PI1-Pad132)") (class "Default")
      (node (ref "Q1") (pin "132") (pinfunction "PI1_132") (pintype "bidirectional"))
    )
    (net (code "187") (name "unconnected-(Q1A-PI2-Pad133)") (class "Default")
      (node (ref "Q1") (pin "133") (pinfunction "PI2_133") (pintype "bidirectional"))
    )
    (net (code "188") (name "unconnected-(Q1A-PI3-Pad134)") (class "Default")
      (node (ref "Q1") (pin "134") (pinfunction "PI3_134") (pintype "bidirectional"))
    )
    (net (code "189") (name "unconnected-(Q1A-PI4-Pad173)") (class "Default")
      (node (ref "Q1") (pin "173") (pinfunction "PI4_173") (pintype "bidirectional"))
    )
    (net (code "190") (name "unconnected-(Q1A-PI5-Pad174)") (class "Default")
      (node (ref "Q1") (pin "174") (pinfunction "PI5_174") (pintype "bidirectional"))
    )
    (net (code "191") (name "unconnected-(Q1A-PI6-Pad175)") (class "Default")
      (node (ref "Q1") (pin "175") (pinfunction "PI6_175") (pintype "bidirectional"))
    )
    (net (code "192") (name "unconnected-(Q1A-PI7-Pad176)") (class "Default")
      (node (ref "Q1") (pin "176") (pinfunction "PI7_176") (pintype "bidirectional"))
    )
    (net (code "193") (name "unconnected-(Q1A-PI8-Pad7)") (class "Default")
      (node (ref "Q1") (pin "7") (pinfunction "PI8_7") (pintype "bidirectional"))
    )
    (net (code "194") (name "unconnected-(Q1A-PI9-Pad11)") (class "Default")
      (node (ref "Q1") (pin "11") (pinfunction "PI9_11") (pintype "bidirectional"))
    )
    (net (code "195") (name "unconnected-(Q1A-PI10-Pad12)") (class "Default")
      (node (ref "Q1") (pin "12") (pinfunction "PI10_12") (pintype "bidirectional"))
    )
    (net (code "196") (name "unconnected-(Q1A-PI11-Pad13)") (class "Default")
      (node (ref "Q1") (pin "13") (pinfunction "PI11_13") (pintype "bidirectional"))
    )
    (net (code "197") (name "unconnected-(Q1B-VCAP1-Pad81)") (class "Default")
      (node (ref "Q1") (pin "81") (pinfunction "VCAP1_81") (pintype "output"))
    )
    (net (code "198") (name "unconnected-(Q1B-VCAP2-Pad125)") (class "Default")
      (node (ref "Q1") (pin "125") (pinfunction "VCAP2_125") (pintype "output"))
    )
    (net (code "199") (name "unconnected-(Q1B-VREF+-Pad38)") (class "Default")
      (node (ref "Q1") (pin "38") (pinfunction "VREF+_38") (pintype "input"))
    )
  )
)
